# ProPrj_GesturePot_2025-03-16.net
KiCad netlist of a schematic drawn in EasyEDA Pro
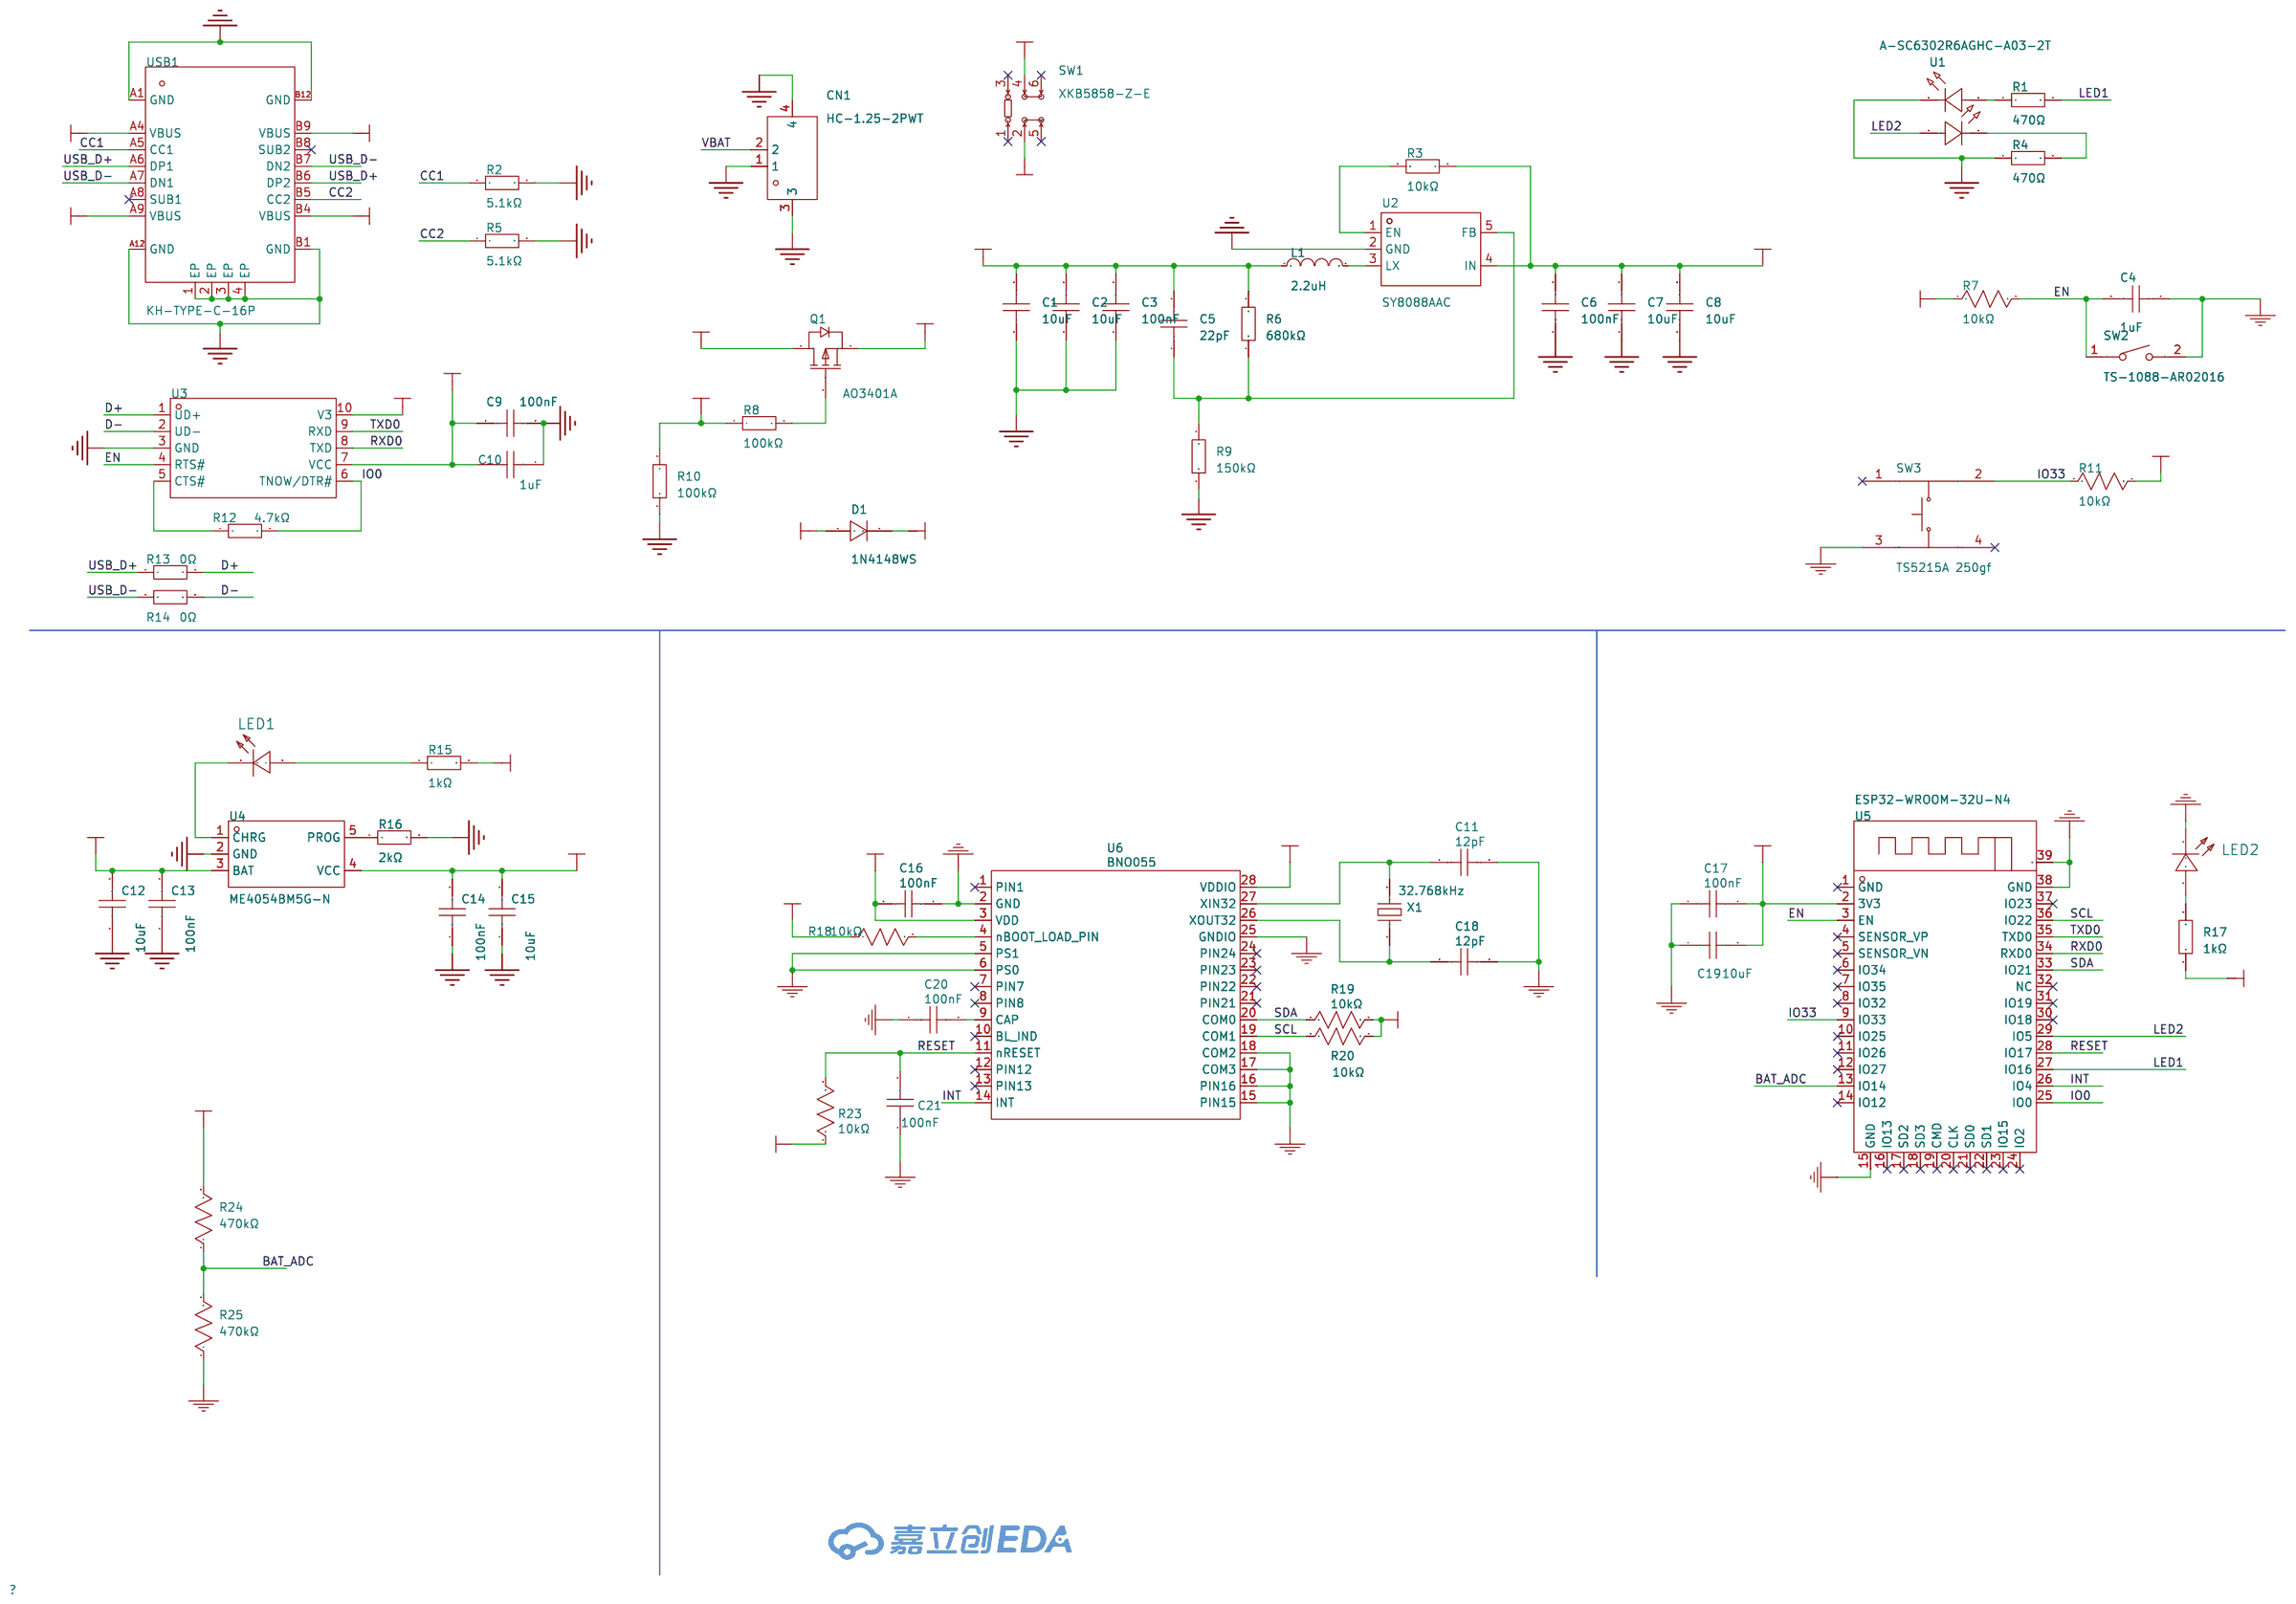
[diagram p0: schematic sheet]

(export (version "E")
  (design (tool "Eeschema 10.0.6"))
  (components
    (comp (ref "C1")
      (value "10uF")
      (fields
        (field (name "Manufacturer Part") "CL10A106KP8NNNC")
        (field (name "Manufacturer") "SAMSUNG(三星)")
      )
      (libsource (lib "easyedapro") (part "CapAcitance"))
    )
    (comp (ref "C2")
      (value "10uF")
      (fields
        (field (name "Manufacturer Part") "CL10A106KP8NNNC")
        (field (name "Manufacturer") "SAMSUNG(三星)")
      )
      (libsource (lib "easyedapro") (part "CapAcitance"))
    )
    (comp (ref "C3")
      (value "100nF")
      (fields
        (field (name "Manufacturer Part") "CC0603KRX7R9BB104")
        (field (name "Manufacturer") "YAGEO(国巨)")
      )
      (libsource (lib "easyedapro") (part "CapAcitance"))
    )
    (comp (ref "C4")
      (value "1uF")
      (footprint "easyedapro:C0603")
      (fields
        (field (name "Manufacturer Part") "CL05A105KA5NQNC")
        (field (name "Manufacturer") "SAMSUNG(三星)")
      )
      (libsource (lib "easyedapro") (part "1uF"))
    )
    (comp (ref "C5")
      (value "22pF")
      (fields
        (field (name "Manufacturer Part") "CL10C220JB8NNNC")
        (field (name "Manufacturer") "SAMSUNG(三星)")
      )
      (libsource (lib "easyedapro") (part "CapAcitance"))
    )
    (comp (ref "C6")
      (value "100nF")
      (fields
        (field (name "Manufacturer Part") "CC0603KRX7R9BB104")
        (field (name "Manufacturer") "YAGEO(国巨)")
      )
      (libsource (lib "easyedapro") (part "CapAcitance"))
    )
    (comp (ref "C7")
      (value "10uF")
      (fields
        (field (name "Manufacturer Part") "CL10A106KP8NNNC")
        (field (name "Manufacturer") "SAMSUNG(三星)")
      )
      (libsource (lib "easyedapro") (part "CapAcitance"))
    )
    (comp (ref "C8")
      (value "10uF")
      (fields
        (field (name "Manufacturer Part") "CL10A106KP8NNNC")
        (field (name "Manufacturer") "SAMSUNG(三星)")
      )
      (libsource (lib "easyedapro") (part "CapAcitance"))
    )
    (comp (ref "C9")
      (value "100nF")
      (fields
        (field (name "Manufacturer Part") "CL05B104KO5NNNC")
        (field (name "Manufacturer") "SAMSUNG(三星)")
      )
      (libsource (lib "easyedapro") (part "CapAcitance"))
    )
    (comp (ref "C10")
      (value "1uF")
      (fields
        (field (name "Manufacturer Part") "CL05A105KA5NQNC")
        (field (name "Manufacturer") "SAMSUNG(三星)")
      )
      (libsource (lib "easyedapro") (part "CapAcitance"))
    )
    (comp (ref "C11")
      (value "12pF")
      (footprint "easyedapro:C0603")
      (fields (field (name "Manufacturer Part") "0402CG120J500NT") (field (name "Manufacturer") "FH(风华)"))
      (libsource (lib "easyedapro") (part "12pF"))
    )
    (comp (ref "C12")
      (value "10uF")
      (fields
        (field (name "Manufacturer Part") "CL10A106KP8NNNC")
        (field (name "Manufacturer") "SAMSUNG(三星)")
      )
      (libsource (lib "easyedapro") (part "CapAcitance"))
    )
    (comp (ref "C13")
      (value "100nF")
      (fields
        (field (name "Manufacturer Part") "CC0603KRX7R9BB104")
        (field (name "Manufacturer") "YAGEO(国巨)")
      )
      (libsource (lib "easyedapro") (part "CapAcitance"))
    )
    (comp (ref "C14")
      (value "100nF")
      (fields
        (field (name "Manufacturer Part") "CC0603KRX7R9BB104")
        (field (name "Manufacturer") "YAGEO(国巨)")
      )
      (libsource (lib "easyedapro") (part "CapAcitance"))
    )
    (comp (ref "C15")
      (value "10uF")
      (fields
        (field (name "Manufacturer Part") "CL10A106KP8NNNC")
        (field (name "Manufacturer") "SAMSUNG(三星)")
      )
      (libsource (lib "easyedapro") (part "CapAcitance"))
    )
    (comp (ref "C16")
      (value "100nF")
      (footprint "easyedapro:C0603")
      (fields
        (field (name "Manufacturer Part") "CL05B104KO5NNNC")
        (field (name "Manufacturer") "SAMSUNG(三星)")
      )
      (libsource (lib "easyedapro") (part "100nF"))
    )
    (comp (ref "C17")
      (value "100nF")
      (footprint "easyedapro:C0603")
      (fields
        (field (name "Manufacturer Part") "CL05B104KO5NNNC")
        (field (name "Manufacturer") "SAMSUNG(三星)")
      )
      (libsource (lib "easyedapro") (part "100nF"))
    )
    (comp (ref "C18")
      (value "12pF")
      (footprint "easyedapro:C0603")
      (fields (field (name "Manufacturer Part") "0402CG120J500NT") (field (name "Manufacturer") "FH(风华)"))
      (libsource (lib "easyedapro") (part "12pF"))
    )
    (comp (ref "C19")
      (value "10uF")
      (footprint "easyedapro:C0603")
      (fields
        (field (name "Manufacturer Part") "CL05A106MQ5NUNC")
        (field (name "Manufacturer") "SAMSUNG(三星)")
      )
      (libsource (lib "easyedapro") (part "10uF"))
    )
    (comp (ref "C20")
      (value "100nF")
      (footprint "easyedapro:C0603")
      (fields
        (field (name "Manufacturer Part") "CL05B104KO5NNNC")
        (field (name "Manufacturer") "SAMSUNG(三星)")
      )
      (libsource (lib "easyedapro") (part "100nF"))
    )
    (comp (ref "C21")
      (value "100nF")
      (footprint "easyedapro:C0603")
      (fields
        (field (name "Manufacturer Part") "CL05B104KO5NNNC")
        (field (name "Manufacturer") "SAMSUNG(三星)")
      )
      (libsource (lib "easyedapro") (part "100nF"))
    )
    (comp (ref "CN1")
      (value "HC-1.25-2PWT")
      (footprint "easyedapro:CONN-SMD_2P-P1.25-HC-1.25-2PWT")
      (fields (field (name "Manufacturer") "HCTL(华灿天禄)"))
      (libsource (lib "easyedapro") (part "HC-1.25-2PWT"))
    )
    (comp (ref "D1")
      (value "1N4148WS")
      (footprint "easyedapro:SOD-323_L1.8-W1.3-LS2.5-RD")
      (description "二极管配置:独立式;正向压降(Vf):1.25V@150mA;直流反向耐压(Vr):100V;整流电流:150mA;反向恢复时间(trr):4ns;")
      (fields (field (name "Manufacturer") "CJ(江苏长电/长晶)"))
      (libsource (lib "easyedapro") (part "1N4148WS T4"))
    )
    (comp (ref "L1")
      (value "2.2uH")
      (fields (field (name "Manufacturer Part") "CMH160808B2R2MT") (field (name "Manufacturer") "FH(风华)"))
      (libsource (lib "easyedapro") (part "SDFL1608S100KTF"))
    )
    (comp (ref "LED1")
      (value "KT-0603R")
      (footprint "easyedapro:LED0603-RD")
      (description "发光颜色:红色;功率:-;正向电流:-;主波长:-;二极管配置:-;透镜颜色:-;色温:-;发光角度:-;载带方式:-;工作温度:-40°C~+85°C;")
      (fields (field (name "Manufacturer") "KENTO"))
      (libsource (lib "easyedapro") (part "KT-0603R"))
    )
    (comp (ref "LED2")
      (value "KT-0603R")
      (footprint "easyedapro:LED0603-RD")
      (description "发光颜色:红色;功率:-;正向电流:-;主波长:-;二极管配置:-;透镜颜色:-;色温:-;发光角度:-;载带方式:-;工作温度:-40°C~+85°C;")
      (fields (field (name "Manufacturer") "KENTO"))
      (libsource (lib "easyedapro") (part "KT-0603R"))
    )
    (comp (ref "Q1")
      (value "AO3401A")
      (footprint "easyedapro:SOT-23_L2.9-W1.3-P1.90-LS2.4-BR")
      (fields (field (name "Manufacturer") "AOS"))
      (libsource (lib "easyedapro") (part "AO3401A"))
    )
    (comp (ref "R1")
      (value "470Ω")
      (footprint "easyedapro:R0603_2")
      (description "电阻类型:厚膜电阻;阻值:1kΩ;精度:±1%;功率:100mW;最大工作电压:75V;温度系数:±100ppm/°C;")
      (fields
        (field (name "Manufacturer Part") "0402WGF4700TCE")
        (field (name "Manufacturer") "UNI-ROYAL(厚声)")
      )
      (libsource (lib "easyedapro") (part "0603WAF1001T5E"))
    )
    (comp (ref "R2")
      (value "5.1kΩ")
      (fields
        (field (name "Manufacturer Part") "0402WGF5101TCE")
        (field (name "Manufacturer") "UNI-ROYAL(厚声)")
      )
      (libsource (lib "easyedapro") (part "电阻_1"))
    )
    (comp (ref "R3")
      (value "10kΩ")
      (fields
        (field (name "Manufacturer Part") "0402WGF1002TCE")
        (field (name "Manufacturer") "UNI-ROYAL(厚声)")
      )
      (libsource (lib "easyedapro") (part "电阻_1"))
    )
    (comp (ref "R4")
      (value "470Ω")
      (footprint "easyedapro:R0603_2")
      (description "电阻类型:厚膜电阻;阻值:1kΩ;精度:±1%;功率:100mW;最大工作电压:75V;温度系数:±100ppm/°C;")
      (fields
        (field (name "Manufacturer Part") "0402WGF4700TCE")
        (field (name "Manufacturer") "UNI-ROYAL(厚声)")
      )
      (libsource (lib "easyedapro") (part "0603WAF1001T5E"))
    )
    (comp (ref "R5")
      (value "5.1kΩ")
      (fields
        (field (name "Manufacturer Part") "0402WGF5101TCE")
        (field (name "Manufacturer") "UNI-ROYAL(厚声)")
      )
      (libsource (lib "easyedapro") (part "电阻_1"))
    )
    (comp (ref "R6")
      (value "680kΩ")
      (footprint "easyedapro:R0603_2")
      (description "电阻类型:厚膜电阻;阻值:680kΩ;精度:±1%;功率:100mW;最大工作电压:75V;温度系数:±100ppm/°C;")
      (fields (field (name "Manufacturer Part") "RC0402FR-07680KL") (field (name "Manufacturer") "YAGEO(国巨)"))
      (libsource (lib "easyedapro") (part "0603WAF6803T5E"))
    )
    (comp (ref "R7")
      (value "10kΩ")
      (footprint "easyedapro:R0603")
      (fields
        (field (name "Manufacturer Part") "0402WGF1002TCE")
        (field (name "Manufacturer") "UNI-ROYAL(厚声)")
      )
      (libsource (lib "easyedapro") (part "10k"))
    )
    (comp (ref "R8")
      (value "100kΩ")
      (footprint "easyedapro:R0603_2")
      (description "电阻类型:厚膜电阻;阻值:100kΩ;精度:±1%;功率:100mW;最大工作电压:75V;温度系数:±100ppm/°C;")
      (fields
        (field (name "Manufacturer Part") "0402WGF1003TCE")
        (field (name "Manufacturer") "UNI-ROYAL(厚声)")
      )
      (libsource (lib "easyedapro") (part "0603WAF1003T5E"))
    )
    (comp (ref "R9")
      (value "150kΩ")
      (footprint "easyedapro:R0603_2")
      (description "电阻类型:厚膜电阻;阻值:150kΩ;精度:±1%;功率:100mW;最大工作电压:75V;温度系数:±100ppm/°C;")
      (fields
        (field (name "Manufacturer Part") "0402WGF1503TCE")
        (field (name "Manufacturer") "UNI-ROYAL(厚声)")
      )
      (libsource (lib "easyedapro") (part "0603WAF1503T5E"))
    )
    (comp (ref "R10")
      (value "100kΩ")
      (footprint "easyedapro:R0603_2")
      (description "电阻类型:厚膜电阻;阻值:100kΩ;精度:±1%;功率:100mW;最大工作电压:75V;温度系数:±100ppm/°C;")
      (fields
        (field (name "Manufacturer Part") "0402WGF1003TCE")
        (field (name "Manufacturer") "UNI-ROYAL(厚声)")
      )
      (libsource (lib "easyedapro") (part "0603WAF1003T5E"))
    )
    (comp (ref "R11")
      (value "10kΩ")
      (footprint "easyedapro:R0603")
      (fields
        (field (name "Manufacturer Part") "0402WGF1002TCE")
        (field (name "Manufacturer") "UNI-ROYAL(厚声)")
      )
      (libsource (lib "easyedapro") (part "10k"))
    )
    (comp (ref "R12")
      (value "4.7kΩ")
      (footprint "easyedapro:R0603")
      (fields
        (field (name "Manufacturer Part") "0402WGF4701TCE")
        (field (name "Manufacturer") "UNI-ROYAL(厚声)")
      )
      (libsource (lib "easyedapro") (part "电阻"))
    )
    (comp (ref "R13")
      (value "0Ω")
      (footprint "easyedapro:R0603")
      (fields
        (field (name "Manufacturer Part") "0402WGF0000TCE")
        (field (name "Manufacturer") "UNI-ROYAL(厚声)")
      )
      (libsource (lib "easyedapro") (part "电阻"))
    )
    (comp (ref "R14")
      (value "0Ω")
      (footprint "easyedapro:R0603")
      (fields
        (field (name "Manufacturer Part") "0402WGF0000TCE")
        (field (name "Manufacturer") "UNI-ROYAL(厚声)")
      )
      (libsource (lib "easyedapro") (part "电阻"))
    )
    (comp (ref "R15")
      (value "1kΩ")
      (footprint "easyedapro:R0603_2")
      (description "电阻类型:厚膜电阻;阻值:1kΩ;精度:±1%;功率:100mW;最大工作电压:75V;温度系数:±100ppm/°C;")
      (fields
        (field (name "Manufacturer Part") "0402WGF1001TCE")
        (field (name "Manufacturer") "UNI-ROYAL(厚声)")
      )
      (libsource (lib "easyedapro") (part "0603WAF1001T5E"))
    )
    (comp (ref "R16")
      (value "2kΩ")
      (footprint "easyedapro:R0603_2")
      (description "电阻类型:厚膜电阻;阻值:2kΩ;精度:±1%;功率:100mW;最大工作电压:75V;温度系数:±100ppm/°C;")
      (fields
        (field (name "Manufacturer Part") "0402WGF2001TCE")
        (field (name "Manufacturer") "UNI-ROYAL(厚声)")
      )
      (libsource (lib "easyedapro") (part "0603WAF2001T5E"))
    )
    (comp (ref "R17")
      (value "1kΩ")
      (footprint "easyedapro:R0603_2")
      (description "电阻类型:厚膜电阻;阻值:1kΩ;精度:±1%;功率:100mW;最大工作电压:75V;温度系数:±100ppm/°C;")
      (fields
        (field (name "Manufacturer Part") "0402WGF1001TCE")
        (field (name "Manufacturer") "UNI-ROYAL(厚声)")
      )
      (libsource (lib "easyedapro") (part "0603WAF1001T5E"))
    )
    (comp (ref "R18")
      (value "10kΩ")
      (footprint "easyedapro:R0603")
      (fields
        (field (name "Manufacturer Part") "0402WGF1002TCE")
        (field (name "Manufacturer") "UNI-ROYAL(厚声)")
      )
      (libsource (lib "easyedapro") (part "10k"))
    )
    (comp (ref "R19")
      (value "10kΩ")
      (footprint "easyedapro:R0603")
      (fields
        (field (name "Manufacturer Part") "0402WGF1002TCE")
        (field (name "Manufacturer") "UNI-ROYAL(厚声)")
      )
      (libsource (lib "easyedapro") (part "10k"))
    )
    (comp (ref "R20")
      (value "10kΩ")
      (footprint "easyedapro:R0603")
      (fields
        (field (name "Manufacturer Part") "0402WGF1002TCE")
        (field (name "Manufacturer") "UNI-ROYAL(厚声)")
      )
      (libsource (lib "easyedapro") (part "10k"))
    )
    (comp (ref "R23")
      (value "10kΩ")
      (footprint "easyedapro:R0603")
      (fields
        (field (name "Manufacturer Part") "0402WGF1002TCE")
        (field (name "Manufacturer") "UNI-ROYAL(厚声)")
      )
      (libsource (lib "easyedapro") (part "10k"))
    )
    (comp (ref "R24")
      (value "470kΩ")
      (footprint "easyedapro:R0603")
      (fields
        (field (name "Manufacturer Part") "0402WGF4703TCE")
        (field (name "Manufacturer") "UNI-ROYAL(厚声)")
      )
      (libsource (lib "easyedapro") (part "10k"))
    )
    (comp (ref "R25")
      (value "470kΩ")
      (footprint "easyedapro:R0603")
      (fields
        (field (name "Manufacturer Part") "0402WGF4703TCE")
        (field (name "Manufacturer") "UNI-ROYAL(厚声)")
      )
      (libsource (lib "easyedapro") (part "10k"))
    )
    (comp (ref "SW1")
      (value "XKB5858-Z-E")
      (footprint "easyedapro:SW-TH_XKB5858-Z-E")
      (description "自锁/无锁:自锁;安装方式:卧插;触点电流:100mA;额定电压 (AC):250V;额定电压 (DC):30V;带灯:不带;作用力:2.5N;机械寿命:10万次;")
      (fields (field (name "Manufacturer") "XKB Connection(中国星坤)"))
      (libsource (lib "easyedapro") (part "XKB5858-Z-E"))
    )
    (comp (ref "SW2")
      (value "TS-1088-AR02016")
      (footprint "easyedapro:SW-SMD_L3.9-W3.0-P4.45")
      (fields (field (name "Manufacturer") "XUNPU(讯普)"))
      (libsource (lib "easyedapro") (part "TS-1088-AR02016"))
    )
    (comp (ref "SW3")
      (value "TS5215A 250gf")
      (footprint "easyedapro:SW-SMD_4P-L5.2-W5.2-P3.70-LS6.4")
      (description "电路结构:单刀单掷;按钮形状:圆形按钮;安装方式:立贴;开关长度:5.2mm;开关宽度:5.2mm;触点电流:50mA;额定电压(DC):12V;带灯:-;机械寿命:-;")
      (fields (field (name "Manufacturer") "SHOU HAN(首韩)"))
      (libsource (lib "easyedapro") (part "TS5215A 250GF"))
    )
    (comp (ref "U1")
      (value "A-SC6302R6AGHC-A03-2T")
      (footprint "easyedapro:LED-SMD_4P-L3.2-W2.8-TR_A-SC6303R6G2B1W")
      (fields (field (name "Manufacturer") "Amicc(欧密格光电)"))
      (libsource (lib "easyedapro") (part "A-SC6302R6AGHC-A03-2T"))
    )
    (comp (ref "U2")
      (value "SY8088AAC")
      (footprint "easyedapro:SOT-23-5_L3.0-W1.7-P0.95-LS2.8-BR")
      (description "功能类型:降压型;输出类型:-;工作电压:2.5V~5.5V;输出电压:-;输出电流:-;")
      (fields (field (name "Manufacturer") "silergy(矽力杰)"))
      (libsource (lib "easyedapro") (part "SY8088AAC"))
    )
    (comp (ref "U3")
      (value "CH340X")
      (footprint "easyedapro:MSOP-10_L3.0-W3.0-P0.50-LS5.0-BL")
      (fields (field (name "Manufacturer") "WCH(南京沁恒)"))
      (libsource (lib "easyedapro") (part "CH340X"))
    )
    (comp (ref "U4")
      (value "ME4054BM5G-N")
      (footprint "easyedapro:TSOT-23-5_L2.9-W1.6-P0.95-LS2.8-BL")
      (fields (field (name "Manufacturer") "MICRONE(南京微盟)"))
      (libsource (lib "easyedapro") (part "ME4054BM5G-N"))
    )
    (comp (ref "U5")
      (value "ESP32-WROOM-32U-N4")
      (footprint "easyedapro:WIFIM-SMD_38P-L19.2-W18.0-P1.27")
      (description "通用型Wi-Fi+BT+BLE MCU模组")
      (fields (field (name "Manufacturer") "ESPRESSIF(乐鑫)"))
      (libsource (lib "easyedapro") (part "ESP32-WROOM-32U"))
    )
    (comp (ref "U6")
      (value "BNO055")
      (footprint "easyedapro:LGA-28_L5.2-W3.8-P0.50-BL")
      (fields (field (name "Manufacturer") "Bosch(博世)") (field (name "Contributor") "LCSC"))
      (libsource (lib "easyedapro") (part "BNO055"))
    )
    (comp (ref "USB1")
      (value "KH-TYPE-C-16P")
      (footprint "easyedapro:USB-C-SMD_KH-TYPE-C-16P")
      (description "连接器类型:Type-C;标准:-;公母:母;端口数量:1;触点数量:16P;安装方式:卧贴;额定电流 - 电源:3A;工作温度范围:-40°C~+85°C;")
      (fields (field (name "Manufacturer") "kinghelm(金航标)"))
      (libsource (lib "easyedapro") (part "KH-TYPE-C-16P"))
    )
    (comp (ref "X1")
      (value "32.768kHz")
      (footprint "easyedapro:OSC-SMD_L3.2-W1.5")
      (description "晶振类型:贴片晶振;频率:32.768kHz;常温频差:±20ppm;外接负载电容:12.5pF;频率稳定度(全温):-;")
      (fields (field (name "Manufacturer Part") "X321532768KGD2SI") (field (name "Manufacturer") "YXC(扬兴晶振)"))
      (libsource (lib "easyedapro") (part "X321532768KGD2SI"))
    )
  )
  (nets
    (net (code "1") (name "/BAT_ADC") (class "Default")
      (node (ref "R24") (pin "1") (pinfunction "1_1") (pintype "unspecified"))
      (node (ref "R25") (pin "2") (pinfunction "2_2") (pintype "unspecified"))
      (node (ref "U5") (pin "13") (pinfunction "IO14_13") (pintype "unspecified"))
    )
    (net (code "2") (name "/CC1") (class "Default")
      (node (ref "R2") (pin "1") (pinfunction "1_1") (pintype "input"))
      (node (ref "USB1") (pin "A5") (pinfunction "CC1_A5") (pintype "unspecified"))
    )
    (net (code "3") (name "/CC2") (class "Default")
      (node (ref "R5") (pin "1") (pinfunction "1_1") (pintype "input"))
      (node (ref "USB1") (pin "B5") (pinfunction "CC2_B5") (pintype "unspecified"))
    )
    (net (code "4") (name "/D+") (class "Default")
      (node (ref "R13") (pin "2") (pinfunction "2_2") (pintype "input"))
      (node (ref "U3") (pin "1") (pinfunction "UD+_1") (pintype "unspecified"))
    )
    (net (code "5") (name "/D-") (class "Default")
      (node (ref "R14") (pin "2") (pinfunction "2_2") (pintype "input"))
      (node (ref "U3") (pin "2") (pinfunction "UD-_2") (pintype "unspecified"))
    )
    (net (code "6") (name "/EN") (class "Default")
      (node (ref "C4") (pin "2") (pinfunction "2_2") (pintype "unspecified"))
      (node (ref "R7") (pin "2") (pinfunction "2_2") (pintype "unspecified"))
      (node (ref "SW2") (pin "1") (pinfunction "1_1") (pintype "unspecified"))
      (node (ref "U3") (pin "4") (pinfunction "RTS#_4") (pintype "unspecified"))
      (node (ref "U5") (pin "3") (pinfunction "EN_3") (pintype "unspecified"))
    )
    (net (code "7") (name "/INT") (class "Default")
      (node (ref "U5") (pin "26") (pinfunction "IO4_26") (pintype "unspecified"))
      (node (ref "U6") (pin "14") (pinfunction "INT_14") (pintype "unspecified"))
    )
    (net (code "8") (name "/IO0") (class "Default")
      (node (ref "R12") (pin "2") (pinfunction "2_2") (pintype "input"))
      (node (ref "U3") (pin "6") (pinfunction "TNOW/DTR#_6") (pintype "unspecified"))
      (node (ref "U5") (pin "25") (pinfunction "IO0_25") (pintype "unspecified"))
    )
    (net (code "9") (name "/IO33") (class "Default")
      (node (ref "R11") (pin "1") (pinfunction "1_1") (pintype "unspecified"))
      (node (ref "SW3") (pin "2") (pinfunction "2_2") (pintype "unspecified"))
      (node (ref "U5") (pin "9") (pinfunction "IO33_9") (pintype "unspecified"))
    )
    (net (code "10") (name "/LED1") (class "Default")
      (node (ref "R1") (pin "2") (pinfunction "2_2") (pintype "input"))
      (node (ref "U5") (pin "27") (pinfunction "IO16_27") (pintype "unspecified"))
    )
    (net (code "11") (name "/LED2") (class "Default")
      (node (ref "U1") (pin "1") (pinfunction "+_1") (pintype "unspecified"))
      (node (ref "U5") (pin "29") (pinfunction "IO5_29") (pintype "unspecified"))
    )
    (net (code "12") (name "/RESET") (class "Default")
      (node (ref "C21") (pin "2") (pinfunction "2_2") (pintype "unspecified"))
      (node (ref "R23") (pin "2") (pinfunction "2_2") (pintype "unspecified"))
      (node (ref "U5") (pin "28") (pinfunction "IO17_28") (pintype "unspecified"))
      (node (ref "U6") (pin "11") (pinfunction "nRESET_11") (pintype "unspecified"))
    )
    (net (code "13") (name "/RXD0") (class "Default")
      (node (ref "U3") (pin "8") (pinfunction "TXD_8") (pintype "unspecified"))
      (node (ref "U5") (pin "34") (pinfunction "RXD0_34") (pintype "unspecified"))
    )
    (net (code "14") (name "/SCL") (class "Default")
      (node (ref "R20") (pin "1") (pinfunction "1_1") (pintype "unspecified"))
      (node (ref "U5") (pin "36") (pinfunction "IO22_36") (pintype "unspecified"))
      (node (ref "U6") (pin "19") (pinfunction "COM1_19") (pintype "unspecified"))
    )
    (net (code "15") (name "/SDA") (class "Default")
      (node (ref "R19") (pin "1") (pinfunction "1_1") (pintype "unspecified"))
      (node (ref "U5") (pin "33") (pinfunction "IO21_33") (pintype "unspecified"))
      (node (ref "U6") (pin "20") (pinfunction "COM0_20") (pintype "unspecified"))
    )
    (net (code "16") (name "/TXD0") (class "Default")
      (node (ref "U3") (pin "9") (pinfunction "RXD_9") (pintype "unspecified"))
      (node (ref "U5") (pin "35") (pinfunction "TXD0_35") (pintype "unspecified"))
    )
    (net (code "17") (name "/USB_D+") (class "Default")
      (node (ref "R13") (pin "1") (pinfunction "1_1") (pintype "input"))
      (node (ref "USB1") (pin "A6") (pinfunction "DP1_A6") (pintype "unspecified"))
      (node (ref "USB1") (pin "B6") (pinfunction "DP2_B6") (pintype "unspecified"))
    )
    (net (code "18") (name "/USB_D-") (class "Default")
      (node (ref "R14") (pin "1") (pinfunction "1_1") (pintype "input"))
      (node (ref "USB1") (pin "A7") (pinfunction "DN1_A7") (pintype "unspecified"))
      (node (ref "USB1") (pin "B7") (pinfunction "DN2_B7") (pintype "unspecified"))
    )
    (net (code "19") (name "GND") (class "Default")
      (node (ref "C1") (pin "1") (pinfunction "1_1") (pintype "input"))
      (node (ref "C10") (pin "2") (pinfunction "2_2") (pintype "input"))
      (node (ref "C11") (pin "2") (pinfunction "2_2") (pintype "unspecified"))
      (node (ref "C12") (pin "1") (pinfunction "1_1") (pintype "input"))
      (node (ref "C13") (pin "1") (pinfunction "1_1") (pintype "input"))
      (node (ref "C14") (pin "1") (pinfunction "1_1") (pintype "input"))
      (node (ref "C15") (pin "1") (pinfunction "1_1") (pintype "input"))
      (node (ref "C16") (pin "1") (pinfunction "1_1") (pintype "unspecified"))
      (node (ref "C17") (pin "1") (pinfunction "1_1") (pintype "unspecified"))
      (node (ref "C18") (pin "2") (pinfunction "2_2") (pintype "unspecified"))
      (node (ref "C19") (pin "1") (pinfunction "1_1") (pintype "unspecified"))
      (node (ref "C2") (pin "1") (pinfunction "1_1") (pintype "input"))
      (node (ref "C20") (pin "1") (pinfunction "1_1") (pintype "unspecified"))
      (node (ref "C21") (pin "1") (pinfunction "1_1") (pintype "unspecified"))
      (node (ref "C3") (pin "1") (pinfunction "1_1") (pintype "input"))
      (node (ref "C4") (pin "1") (pinfunction "1_1") (pintype "unspecified"))
      (node (ref "C6") (pin "1") (pinfunction "1_1") (pintype "input"))
      (node (ref "C7") (pin "1") (pinfunction "1_1") (pintype "input"))
      (node (ref "C8") (pin "1") (pinfunction "1_1") (pintype "input"))
      (node (ref "C9") (pin "2") (pinfunction "2_2") (pintype "input"))
      (node (ref "CN1") (pin "1") (pinfunction "1_1") (pintype "unspecified"))
      (node (ref "CN1") (pin "3") (pinfunction "3_3") (pintype "unspecified"))
      (node (ref "CN1") (pin "4") (pinfunction "4_4") (pintype "unspecified"))
      (node (ref "LED2") (pin "1") (pinfunction "K_1") (pintype "unspecified"))
      (node (ref "R10") (pin "1") (pinfunction "1_1") (pintype "input"))
      (node (ref "R16") (pin "2") (pinfunction "2_2") (pintype "input"))
      (node (ref "R2") (pin "2") (pinfunction "2_2") (pintype "input"))
      (node (ref "R25") (pin "1") (pinfunction "1_1") (pintype "unspecified"))
      (node (ref "R4") (pin "1") (pinfunction "1_1") (pintype "input"))
      (node (ref "R5") (pin "2") (pinfunction "2_2") (pintype "input"))
      (node (ref "R9") (pin "2") (pinfunction "2_2") (pintype "input"))
      (node (ref "SW2") (pin "2") (pinfunction "2_2") (pintype "unspecified"))
      (node (ref "SW3") (pin "3") (pinfunction "3_3") (pintype "unspecified"))
      (node (ref "U1") (pin "2") (pinfunction "-_2") (pintype "unspecified"))
      (node (ref "U2") (pin "2") (pinfunction "GND_2") (pintype "unspecified"))
      (node (ref "U3") (pin "3") (pinfunction "GND_3") (pintype "unspecified"))
      (node (ref "U4") (pin "2") (pinfunction "GND_2") (pintype "unspecified"))
      (node (ref "U5") (pin "15") (pinfunction "GND_15") (pintype "unspecified"))
      (node (ref "U5") (pin "38") (pinfunction "GND_38") (pintype "unspecified"))
      (node (ref "U5") (pin "39") (pinfunction "GND_39") (pintype "unspecified"))
      (node (ref "U6") (pin "15") (pinfunction "PIN15_15") (pintype "unspecified"))
      (node (ref "U6") (pin "16") (pinfunction "PIN16_16") (pintype "unspecified"))
      (node (ref "U6") (pin "17") (pinfunction "COM3_17") (pintype "unspecified"))
      (node (ref "U6") (pin "18") (pinfunction "COM2_18") (pintype "unspecified"))
      (node (ref "U6") (pin "2") (pinfunction "GND_2") (pintype "unspecified"))
      (node (ref "U6") (pin "25") (pinfunction "GNDIO_25") (pintype "unspecified"))
      (node (ref "U6") (pin "5") (pinfunction "PS1_5") (pintype "unspecified"))
      (node (ref "U6") (pin "6") (pinfunction "PS0_6") (pintype "unspecified"))
      (node (ref "USB1") (pin "1") (pinfunction "EP_1") (pintype "unspecified"))
      (node (ref "USB1") (pin "2") (pinfunction "EP_2") (pintype "unspecified"))
      (node (ref "USB1") (pin "3") (pinfunction "EP_3") (pintype "unspecified"))
      (node (ref "USB1") (pin "4") (pinfunction "EP_4") (pintype "unspecified"))
      (node (ref "USB1") (pin "A1") (pinfunction "GND_A1") (pintype "unspecified"))
      (node (ref "USB1") (pin "A12") (pinfunction "GND_A12") (pintype "unspecified"))
      (node (ref "USB1") (pin "B1") (pinfunction "GND_B1") (pintype "unspecified"))
      (node (ref "USB1") (pin "B12") (pinfunction "GND_B12") (pintype "unspecified"))
    )
    (net (code "20") (name "Net-(LED1-A)") (class "Default")
      (node (ref "LED1") (pin "2") (pinfunction "A_2") (pintype "unspecified"))
      (node (ref "R15") (pin "1") (pinfunction "1_1") (pintype "input"))
    )
    (net (code "21") (name "Net-(LED1-K)") (class "Default")
      (node (ref "LED1") (pin "1") (pinfunction "K_1") (pintype "unspecified"))
      (node (ref "U4") (pin "1") (pinfunction "CHRG_1") (pintype "unspecified"))
    )
    (net (code "22") (name "Net-(LED2-A)") (class "Default")
      (node (ref "LED2") (pin "2") (pinfunction "A_2") (pintype "unspecified"))
      (node (ref "R17") (pin "2") (pinfunction "2_2") (pintype "input"))
    )
    (net (code "23") (name "Net-(Q1-G)") (class "Default")
      (node (ref "Q1") (pin "1") (pinfunction "G_1") (pintype "unspecified"))
      (node (ref "R8") (pin "2") (pinfunction "2_2") (pintype "input"))
    )
    (net (code "24") (name "Net-(R1-Pad1)") (class "Default")
      (node (ref "R1") (pin "1") (pinfunction "1_1") (pintype "input"))
      (node (ref "U1") (pin "3") (pinfunction "+_3") (pintype "unspecified"))
    )
    (net (code "25") (name "Net-(R4-Pad2)") (class "Default")
      (node (ref "R4") (pin "2") (pinfunction "2_2") (pintype "input"))
      (node (ref "U1") (pin "4") (pinfunction "-_4") (pintype "unspecified"))
    )
    (net (code "26") (name "Net-(U2-EN)") (class "Default")
      (node (ref "R3") (pin "2") (pinfunction "2_2") (pintype "input"))
      (node (ref "U2") (pin "1") (pinfunction "EN_1") (pintype "unspecified"))
    )
    (net (code "27") (name "Net-(U2-FB)") (class "Default")
      (node (ref "C5") (pin "1") (pinfunction "1_1") (pintype "input"))
      (node (ref "R6") (pin "1") (pinfunction "1_1") (pintype "input"))
      (node (ref "R9") (pin "1") (pinfunction "1_1") (pintype "input"))
      (node (ref "U2") (pin "5") (pinfunction "FB_5") (pintype "unspecified"))
    )
    (net (code "28") (name "Net-(U2-LX)") (class "Default")
      (node (ref "L1") (pin "2") (pinfunction "2_2") (pintype "unspecified"))
      (node (ref "U2") (pin "3") (pinfunction "LX_3") (pintype "unspecified"))
    )
    (net (code "29") (name "Net-(U3-CTS#)") (class "Default")
      (node (ref "R12") (pin "1") (pinfunction "1_1") (pintype "input"))
      (node (ref "U3") (pin "5") (pinfunction "CTS#_5") (pintype "unspecified"))
    )
    (net (code "30") (name "Net-(U4-PROG)") (class "Default")
      (node (ref "R16") (pin "1") (pinfunction "1_1") (pintype "input"))
      (node (ref "U4") (pin "5") (pinfunction "PROG_5") (pintype "unspecified"))
    )
    (net (code "31") (name "Net-(U6-CAP)") (class "Default")
      (node (ref "C20") (pin "2") (pinfunction "2_2") (pintype "unspecified"))
      (node (ref "U6") (pin "9") (pinfunction "CAP_9") (pintype "unspecified"))
    )
    (net (code "32") (name "Net-(U6-XIN32)") (class "Default")
      (node (ref "C11") (pin "1") (pinfunction "1_1") (pintype "unspecified"))
      (node (ref "U6") (pin "27") (pinfunction "XIN32_27") (pintype "unspecified"))
      (node (ref "X1") (pin "2") (pinfunction "2_2") (pintype "input"))
    )
    (net (code "33") (name "Net-(U6-XOUT32)") (class "Default")
      (node (ref "C18") (pin "1") (pinfunction "1_1") (pintype "unspecified"))
      (node (ref "U6") (pin "26") (pinfunction "XOUT32_26") (pintype "unspecified"))
      (node (ref "X1") (pin "1") (pinfunction "1_1") (pintype "input"))
    )
    (net (code "34") (name "Net-(U6-nBOOT_LOAD_PIN)") (class "Default")
      (node (ref "R18") (pin "2") (pinfunction "2_2") (pintype "unspecified"))
      (node (ref "U6") (pin "4") (pinfunction "nBOOT_LOAD_PIN_4") (pintype "unspecified"))
    )
    (net (code "35") (name "VBAT") (class "Default")
      (node (ref "C12") (pin "2") (pinfunction "2_2") (pintype "input"))
      (node (ref "C13") (pin "2") (pinfunction "2_2") (pintype "input"))
      (node (ref "CN1") (pin "2") (pinfunction "2_2") (pintype "unspecified"))
      (node (ref "R24") (pin "2") (pinfunction "2_2") (pintype "unspecified"))
      (node (ref "SW1") (pin "2") (pinfunction "2_2") (pintype "unspecified"))
      (node (ref "U4") (pin "3") (pinfunction "BAT_3") (pintype "unspecified"))
    )
    (net (code "36") (name "VBAT_IN") (class "Default")
      (node (ref "Q1") (pin "3") (pinfunction "D_3") (pintype "unspecified"))
      (node (ref "SW1") (pin "4") (pinfunction "4_4") (pintype "unspecified"))
    )
    (net (code "37") (name "VBUS") (class "Default")
      (node (ref "D1") (pin "2") (pinfunction "A_2") (pintype "unspecified"))
      (node (ref "R10") (pin "2") (pinfunction "2_2") (pintype "input"))
      (node (ref "R8") (pin "1") (pinfunction "1_1") (pintype "input"))
      (node (ref "USB1") (pin "A4") (pinfunction "VBUS_A4") (pintype "unspecified"))
      (node (ref "USB1") (pin "A9") (pinfunction "VBUS_A9") (pintype "unspecified"))
      (node (ref "USB1") (pin "B4") (pinfunction "VBUS_B4") (pintype "unspecified"))
      (node (ref "USB1") (pin "B9") (pinfunction "VBUS_B9") (pintype "unspecified"))
    )
    (net (code "38") (name "VCC_3V3") (class "Default")
      (node (ref "C1") (pin "2") (pinfunction "2_2") (pintype "input"))
      (node (ref "C10") (pin "1") (pinfunction "1_1") (pintype "input"))
      (node (ref "C16") (pin "2") (pinfunction "2_2") (pintype "unspecified"))
      (node (ref "C17") (pin "2") (pinfunction "2_2") (pintype "unspecified"))
      (node (ref "C19") (pin "2") (pinfunction "2_2") (pintype "unspecified"))
      (node (ref "C2") (pin "2") (pinfunction "2_2") (pintype "input"))
      (node (ref "C3") (pin "2") (pinfunction "2_2") (pintype "input"))
      (node (ref "C5") (pin "2") (pinfunction "2_2") (pintype "input"))
      (node (ref "C9") (pin "1") (pinfunction "1_1") (pintype "input"))
      (node (ref "L1") (pin "1") (pinfunction "1_1") (pintype "unspecified"))
      (node (ref "R11") (pin "2") (pinfunction "2_2") (pintype "unspecified"))
      (node (ref "R17") (pin "1") (pinfunction "1_1") (pintype "input"))
      (node (ref "R18") (pin "1") (pinfunction "1_1") (pintype "unspecified"))
      (node (ref "R19") (pin "2") (pinfunction "2_2") (pintype "unspecified"))
      (node (ref "R20") (pin "2") (pinfunction "2_2") (pintype "unspecified"))
      (node (ref "R23") (pin "1") (pinfunction "1_1") (pintype "unspecified"))
      (node (ref "R6") (pin "2") (pinfunction "2_2") (pintype "input"))
      (node (ref "R7") (pin "1") (pinfunction "1_1") (pintype "unspecified"))
      (node (ref "U3") (pin "10") (pinfunction "V3_10") (pintype "unspecified"))
      (node (ref "U3") (pin "7") (pinfunction "VCC_7") (pintype "unspecified"))
      (node (ref "U5") (pin "2") (pinfunction "3V3_2") (pintype "unspecified"))
      (node (ref "U6") (pin "28") (pinfunction "VDDIO_28") (pintype "unspecified"))
      (node (ref "U6") (pin "3") (pinfunction "VDD_3") (pintype "unspecified"))
    )
    (net (code "39") (name "VDD") (class "Default")
      (node (ref "C6") (pin "2") (pinfunction "2_2") (pintype "input"))
      (node (ref "C7") (pin "2") (pinfunction "2_2") (pintype "input"))
      (node (ref "C8") (pin "2") (pinfunction "2_2") (pintype "input"))
      (node (ref "D1") (pin "1") (pinfunction "K_1") (pintype "unspecified"))
      (node (ref "Q1") (pin "2") (pinfunction "S_2") (pintype "unspecified"))
      (node (ref "R3") (pin "1") (pinfunction "1_1") (pintype "input"))
      (node (ref "U2") (pin "4") (pinfunction "IN_4") (pintype "unspecified"))
    )
    (net (code "40") (name "VUSB") (class "Default")
      (node (ref "C14") (pin "2") (pinfunction "2_2") (pintype "input"))
      (node (ref "C15") (pin "2") (pinfunction "2_2") (pintype "input"))
      (node (ref "R15") (pin "2") (pinfunction "2_2") (pintype "input"))
      (node (ref "U4") (pin "4") (pinfunction "VCC_4") (pintype "unspecified"))
    )
    (net (code "41") (name "unconnected-(SW1-Pad1)") (class "Default")
      (node (ref "SW1") (pin "1") (pinfunction "1_1") (pintype "unspecified+no_connect"))
    )
    (net (code "42") (name "unconnected-(SW1-Pad3)") (class "Default")
      (node (ref "SW1") (pin "3") (pinfunction "3_3") (pintype "unspecified+no_connect"))
    )
    (net (code "43") (name "unconnected-(SW1-Pad5)") (class "Default")
      (node (ref "SW1") (pin "5") (pinfunction "5_5") (pintype "unspecified+no_connect"))
    )
    (net (code "44") (name "unconnected-(SW1-Pad6)") (class "Default")
      (node (ref "SW1") (pin "6") (pinfunction "6_6") (pintype "unspecified+no_connect"))
    )
    (net (code "45") (name "unconnected-(SW3-Pad1)") (class "Default")
      (node (ref "SW3") (pin "1") (pinfunction "1_1") (pintype "unspecified+no_connect"))
    )
    (net (code "46") (name "unconnected-(SW3-Pad4)") (class "Default")
      (node (ref "SW3") (pin "4") (pinfunction "4_4") (pintype "unspecified+no_connect"))
    )
    (net (code "47") (name "unconnected-(U5-CLK-Pad20)") (class "Default")
      (node (ref "U5") (pin "20") (pinfunction "CLK_20") (pintype "unspecified+no_connect"))
    )
    (net (code "48") (name "unconnected-(U5-CMD-Pad19)") (class "Default")
      (node (ref "U5") (pin "19") (pinfunction "CMD_19") (pintype "unspecified+no_connect"))
    )
    (net (code "49") (name "unconnected-(U5-GND-Pad1)") (class "Default")
      (node (ref "U5") (pin "1") (pinfunction "GND_1") (pintype "unspecified+no_connect"))
    )
    (net (code "50") (name "unconnected-(U5-IO2-Pad24)") (class "Default")
      (node (ref "U5") (pin "24") (pinfunction "IO2_24") (pintype "unspecified+no_connect"))
    )
    (net (code "51") (name "unconnected-(U5-IO12-Pad14)") (class "Default")
      (node (ref "U5") (pin "14") (pinfunction "IO12_14") (pintype "unspecified+no_connect"))
    )
    (net (code "52") (name "unconnected-(U5-IO13-Pad16)") (class "Default")
      (node (ref "U5") (pin "16") (pinfunction "IO13_16") (pintype "unspecified+no_connect"))
    )
    (net (code "53") (name "unconnected-(U5-IO15-Pad23)") (class "Default")
      (node (ref "U5") (pin "23") (pinfunction "IO15_23") (pintype "unspecified+no_connect"))
    )
    (net (code "54") (name "unconnected-(U5-IO18-Pad30)") (class "Default")
      (node (ref "U5") (pin "30") (pinfunction "IO18_30") (pintype "unspecified+no_connect"))
    )
    (net (code "55") (name "unconnected-(U5-IO19-Pad31)") (class "Default")
      (node (ref "U5") (pin "31") (pinfunction "IO19_31") (pintype "unspecified+no_connect"))
    )
    (net (code "56") (name "unconnected-(U5-IO23-Pad37)") (class "Default")
      (node (ref "U5") (pin "37") (pinfunction "IO23_37") (pintype "unspecified+no_connect"))
    )
    (net (code "57") (name "unconnected-(U5-IO25-Pad10)") (class "Default")
      (node (ref "U5") (pin "10") (pinfunction "IO25_10") (pintype "unspecified+no_connect"))
    )
    (net (code "58") (name "unconnected-(U5-IO26-Pad11)") (class "Default")
      (node (ref "U5") (pin "11") (pinfunction "IO26_11") (pintype "unspecified+no_connect"))
    )
    (net (code "59") (name "unconnected-(U5-IO27-Pad12)") (class "Default")
      (node (ref "U5") (pin "12") (pinfunction "IO27_12") (pintype "unspecified+no_connect"))
    )
    (net (code "60") (name "unconnected-(U5-IO32-Pad8)") (class "Default")
      (node (ref "U5") (pin "8") (pinfunction "IO32_8") (pintype "unspecified+no_connect"))
    )
    (net (code "61") (name "unconnected-(U5-IO34-Pad6)") (class "Default")
      (node (ref "U5") (pin "6") (pinfunction "IO34_6") (pintype "unspecified+no_connect"))
    )
    (net (code "62") (name "unconnected-(U5-IO35-Pad7)") (class "Default")
      (node (ref "U5") (pin "7") (pinfunction "IO35_7") (pintype "unspecified+no_connect"))
    )
    (net (code "63") (name "unconnected-(U5-NC-Pad32)") (class "Default")
      (node (ref "U5") (pin "32") (pinfunction "NC_32") (pintype "unspecified+no_connect"))
    )
    (net (code "64") (name "unconnected-(U5-SD0-Pad21)") (class "Default")
      (node (ref "U5") (pin "21") (pinfunction "SD0_21") (pintype "unspecified+no_connect"))
    )
    (net (code "65") (name "unconnected-(U5-SD1-Pad22)") (class "Default")
      (node (ref "U5") (pin "22") (pinfunction "SD1_22") (pintype "unspecified+no_connect"))
    )
    (net (code "66") (name "unconnected-(U5-SD2-Pad17)") (class "Default")
      (node (ref "U5") (pin "17") (pinfunction "SD2_17") (pintype "unspecified+no_connect"))
    )
    (net (code "67") (name "unconnected-(U5-SD3-Pad18)") (class "Default")
      (node (ref "U5") (pin "18") (pinfunction "SD3_18") (pintype "unspecified+no_connect"))
    )
    (net (code "68") (name "unconnected-(U5-SENSOR_VN-Pad5)") (class "Default")
      (node (ref "U5") (pin "5") (pinfunction "SENSOR_VN_5") (pintype "unspecified+no_connect"))
    )
    (net (code "69") (name "unconnected-(U5-SENSOR_VP-Pad4)") (class "Default")
      (node (ref "U5") (pin "4") (pinfunction "SENSOR_VP_4") (pintype "unspecified+no_connect"))
    )
    (net (code "70") (name "unconnected-(U6-BL_IND-Pad10)") (class "Default")
      (node (ref "U6") (pin "10") (pinfunction "BL_IND_10") (pintype "unspecified+no_connect"))
    )
    (net (code "71") (name "unconnected-(U6-PIN1-Pad1)") (class "Default")
      (node (ref "U6") (pin "1") (pinfunction "PIN1_1") (pintype "unspecified+no_connect"))
    )
    (net (code "72") (name "unconnected-(U6-PIN7-Pad7)") (class "Default")
      (node (ref "U6") (pin "7") (pinfunction "PIN7_7") (pintype "unspecified+no_connect"))
    )
    (net (code "73") (name "unconnected-(U6-PIN8-Pad8)") (class "Default")
      (node (ref "U6") (pin "8") (pinfunction "PIN8_8") (pintype "unspecified+no_connect"))
    )
    (net (code "74") (name "unconnected-(U6-PIN12-Pad12)") (class "Default")
      (node (ref "U6") (pin "12") (pinfunction "PIN12_12") (pintype "unspecified+no_connect"))
    )
    (net (code "75") (name "unconnected-(U6-PIN13-Pad13)") (class "Default")
      (node (ref "U6") (pin "13") (pinfunction "PIN13_13") (pintype "unspecified+no_connect"))
    )
    (net (code "76") (name "unconnected-(U6-PIN21-Pad21)") (class "Default")
      (node (ref "U6") (pin "21") (pinfunction "PIN21_21") (pintype "unspecified+no_connect"))
    )
    (net (code "77") (name "unconnected-(U6-PIN22-Pad22)") (class "Default")
      (node (ref "U6") (pin "22") (pinfunction "PIN22_22") (pintype "unspecified+no_connect"))
    )
    (net (code "78") (name "unconnected-(U6-PIN23-Pad23)") (class "Default")
      (node (ref "U6") (pin "23") (pinfunction "PIN23_23") (pintype "unspecified+no_connect"))
    )
    (net (code "79") (name "unconnected-(U6-PIN24-Pad24)") (class "Default")
      (node (ref "U6") (pin "24") (pinfunction "PIN24_24") (pintype "unspecified+no_connect"))
    )
    (net (code "80") (name "unconnected-(USB1-SUB1-PadA8)") (class "Default")
      (node (ref "USB1") (pin "A8") (pinfunction "SUB1_A8") (pintype "unspecified+no_connect"))
    )
    (net (code "81") (name "unconnected-(USB1-SUB2-PadB8)") (class "Default")
      (node (ref "USB1") (pin "B8") (pinfunction "SUB2_B8") (pintype "unspecified+no_connect"))
    )
  )
)
